# untitled.net
KiCad netlist of a schematic drawn in EAGLE
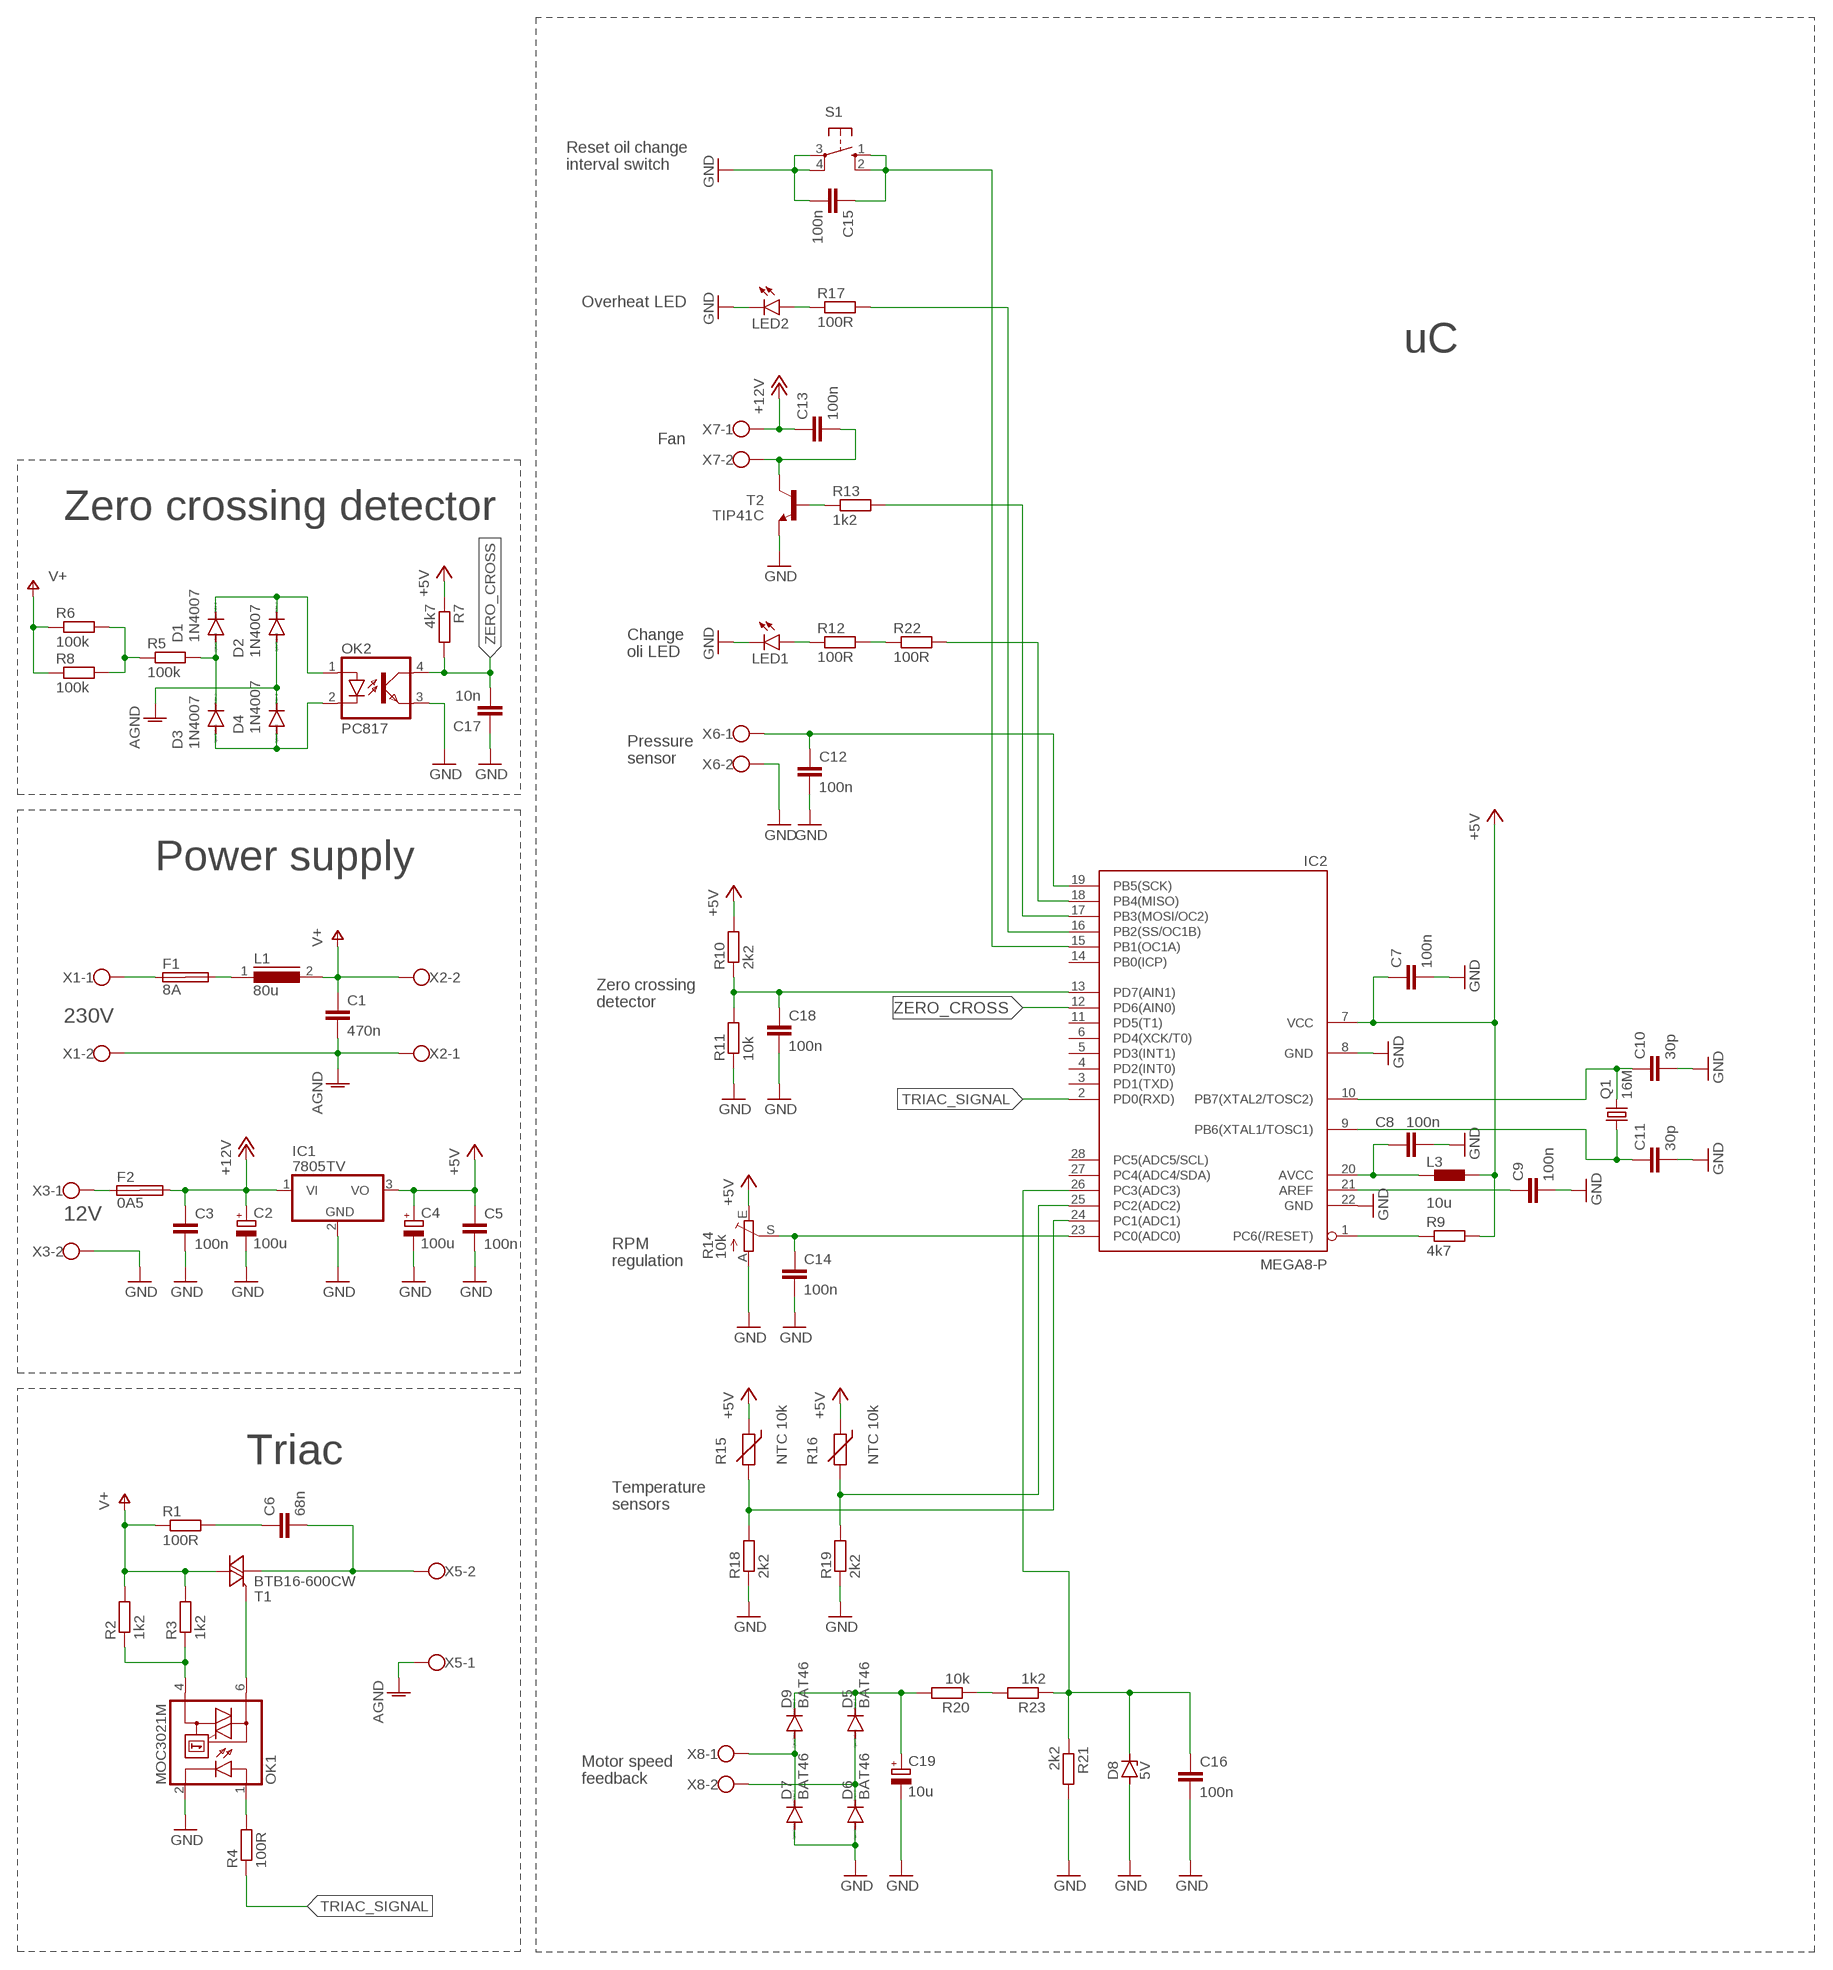
[diagram p0: schematic, sheet 1]

(export (version "E")
  (design (tool "Eeschema 10.0.6"))
  (components
    (comp (ref "C1")
      (value "470n")
      (footprint "eagle-import:C22.5B7")
      (libsource (lib "eagle-import") (part "C22/7"))
    )
    (comp (ref "C2")
      (value "100u")
      (footprint "eagle-import:E3,5-8")
      (libsource (lib "eagle-import") (part "CPOL-EUE3.5-8"))
    )
    (comp (ref "C3")
      (value "100n")
      (footprint "eagle-import:C5B3")
      (libsource (lib "eagle-import") (part "C5/3"))
    )
    (comp (ref "C4")
      (value "100u")
      (footprint "eagle-import:E3,5-8")
      (libsource (lib "eagle-import") (part "CPOL-EUE3.5-8"))
    )
    (comp (ref "C5")
      (value "100n")
      (footprint "eagle-import:C5B3")
      (libsource (lib "eagle-import") (part "C5/3"))
    )
    (comp (ref "C6")
      (value "68n")
      (footprint "eagle-import:C150-084X183")
      (libsource (lib "eagle-import") (part "C-EU150-084X183"))
    )
    (comp (ref "C7")
      (value "100n")
      (footprint "eagle-import:C5B3")
      (libsource (lib "eagle-import") (part "C5/3"))
    )
    (comp (ref "C8")
      (value "100n")
      (footprint "eagle-import:C5B3")
      (libsource (lib "eagle-import") (part "C5/3"))
    )
    (comp (ref "C9")
      (value "100n")
      (footprint "eagle-import:C5B3")
      (libsource (lib "eagle-import") (part "C5/3"))
    )
    (comp (ref "C10")
      (value "30p")
      (footprint "eagle-import:C5B3")
      (libsource (lib "eagle-import") (part "C5/3"))
    )
    (comp (ref "C11")
      (value "30p")
      (footprint "eagle-import:C5B3")
      (libsource (lib "eagle-import") (part "C5/3"))
    )
    (comp (ref "C12")
      (value "100n")
      (footprint "eagle-import:C5B3")
      (libsource (lib "eagle-import") (part "C5/3"))
    )
    (comp (ref "C13")
      (value "100n")
      (footprint "eagle-import:C5B3")
      (libsource (lib "eagle-import") (part "C5/3"))
    )
    (comp (ref "C14")
      (value "100n")
      (footprint "eagle-import:C5B3")
      (libsource (lib "eagle-import") (part "C5/3"))
    )
    (comp (ref "C15")
      (value "100n")
      (footprint "eagle-import:C5B3")
      (libsource (lib "eagle-import") (part "C5/3"))
    )
    (comp (ref "C16")
      (value "100n")
      (footprint "eagle-import:C5B3")
      (libsource (lib "eagle-import") (part "C5/3"))
    )
    (comp (ref "C17")
      (value "10n")
      (footprint "eagle-import:C5B3")
      (libsource (lib "eagle-import") (part "C5/3"))
    )
    (comp (ref "C18")
      (value "100n")
      (footprint "eagle-import:C5B3")
      (libsource (lib "eagle-import") (part "C5/3"))
    )
    (comp (ref "C19")
      (value "10u")
      (footprint "eagle-import:E2,5-6")
      (libsource (lib "eagle-import") (part "CPOL-EUE2.5-6"))
    )
    (comp (ref "D1")
      (value "1N4007")
      (footprint "eagle-import:DO41-10")
      (libsource (lib "eagle-import") (part "1N4933"))
    )
    (comp (ref "D2")
      (value "1N4007")
      (footprint "eagle-import:DO41-10")
      (libsource (lib "eagle-import") (part "1N4933"))
    )
    (comp (ref "D3")
      (value "1N4007")
      (footprint "eagle-import:DO41-10")
      (libsource (lib "eagle-import") (part "1N4933"))
    )
    (comp (ref "D4")
      (value "1N4007")
      (footprint "eagle-import:DO41-10")
      (libsource (lib "eagle-import") (part "1N4933"))
    )
    (comp (ref "D5")
      (value "BAT46")
      (footprint "eagle-import:DO34-7")
      (libsource (lib "eagle-import") (part "BAS15"))
    )
    (comp (ref "D6")
      (value "BAT46")
      (footprint "eagle-import:DO34-7")
      (libsource (lib "eagle-import") (part "BAS15"))
    )
    (comp (ref "D7")
      (value "BAT46")
      (footprint "eagle-import:DO34-7")
      (libsource (lib "eagle-import") (part "BAS15"))
    )
    (comp (ref "D8")
      (value "5V")
      (footprint "eagle-import:DO34Z7")
      (libsource (lib "eagle-import") (part "ZENER-DIODEDO34-7"))
    )
    (comp (ref "D9")
      (value "BAT46")
      (footprint "eagle-import:DO34-7")
      (libsource (lib "eagle-import") (part "BAS15"))
    )
    (comp (ref "F1")
      (value "8A")
      (footprint "eagle-import:SHK20L")
      (libsource (lib "eagle-import") (part "SHK20L"))
    )
    (comp (ref "F2")
      (value "0A5")
      (footprint "eagle-import:SHK20L")
      (libsource (lib "eagle-import") (part "SHK20L"))
    )
    (comp (ref "IC1")
      (value "7805TV")
      (footprint "eagle-import:TO220V")
      (libsource (lib "eagle-import") (part "78TV05"))
    )
    (comp (ref "IC2")
      (value "MEGA8-P")
      (footprint "eagle-import:DIL28-3")
      (libsource (lib "eagle-import") (part "MEGA8-P"))
    )
    (comp (ref "L1")
      (value "80u")
      (footprint "eagle-import:SFT1030")
      (libsource (lib "eagle-import") (part "SFT1030"))
    )
    (comp (ref "L3")
      (value "10u")
      (footprint "eagle-import:BL01RN1A")
      (libsource (lib "eagle-import") (part "BL01RN1A"))
    )
    (comp (ref "LED1")
      (value "LED5MM")
      (footprint "eagle-import:LED5MM")
      (libsource (lib "eagle-import") (part "LED5MM"))
    )
    (comp (ref "LED2")
      (value "LED5MM")
      (footprint "eagle-import:LED5MM")
      (libsource (lib "eagle-import") (part "LED5MM"))
    )
    (comp (ref "OK1")
      (value "MOC3021M")
      (footprint "eagle-import:DIL06")
      (fields (field (name "MF") "FAIRCHILD SEMICONDUCTOR") (field (name "MPN") "MOC3021-M"))
      (libsource (lib "eagle-import") (part "MOC30M21"))
    )
    (comp (ref "OK2")
      (value "PC817")
      (footprint "eagle-import:DIL04")
      (fields (field (name "MPN") "PC817X4J000F"))
      (libsource (lib "eagle-import") (part "PC817"))
    )
    (comp (ref "Q1")
      (value "16M")
      (footprint "eagle-import:HC49_S")
      (libsource (lib "eagle-import") (part "CRYSTALHC49S"))
    )
    (comp (ref "R1")
      (value "100R")
      (footprint "eagle-import:0204_7")
      (libsource (lib "eagle-import") (part "R-EU_0204/7"))
    )
    (comp (ref "R2")
      (value "1k2")
      (footprint "eagle-import:0204_7")
      (libsource (lib "eagle-import") (part "R-EU_0204/7"))
    )
    (comp (ref "R3")
      (value "1k2")
      (footprint "eagle-import:0204_7")
      (libsource (lib "eagle-import") (part "R-EU_0204/7"))
    )
    (comp (ref "R4")
      (value "100R")
      (footprint "eagle-import:0204_7")
      (libsource (lib "eagle-import") (part "R-EU_0204/7"))
    )
    (comp (ref "R5")
      (value "100k")
      (footprint "eagle-import:0204_7")
      (libsource (lib "eagle-import") (part "R-EU_0204/7"))
    )
    (comp (ref "R6")
      (value "100k")
      (footprint "eagle-import:0204_7")
      (libsource (lib "eagle-import") (part "R-EU_0204/7"))
    )
    (comp (ref "R7")
      (value "4k7")
      (footprint "eagle-import:0204_7")
      (libsource (lib "eagle-import") (part "R-EU_0204/7"))
    )
    (comp (ref "R8")
      (value "100k")
      (footprint "eagle-import:0204_7")
      (libsource (lib "eagle-import") (part "R-EU_0204/7"))
    )
    (comp (ref "R9")
      (value "4k7")
      (footprint "eagle-import:0204_7")
      (libsource (lib "eagle-import") (part "R-EU_0204/7"))
    )
    (comp (ref "R10")
      (value "2k2")
      (footprint "eagle-import:0204_7")
      (libsource (lib "eagle-import") (part "R-EU_0204/7"))
    )
    (comp (ref "R11")
      (value "10k")
      (footprint "eagle-import:0204_7")
      (libsource (lib "eagle-import") (part "R-EU_0204/7"))
    )
    (comp (ref "R12")
      (value "100R")
      (footprint "eagle-import:0204_7")
      (libsource (lib "eagle-import") (part "R-EU_0204/7"))
    )
    (comp (ref "R13")
      (value "1k2")
      (footprint "eagle-import:0204_7")
      (libsource (lib "eagle-import") (part "R-EU_0204/7"))
    )
    (comp (ref "R14")
      (value "10k")
      (footprint "eagle-import:RJ9W")
      (libsource (lib "eagle-import") (part "TRIM_EU-RJ9W"))
    )
    (comp (ref "R15")
      (value "NTC 10k")
      (footprint "eagle-import:R-7,5")
      (libsource (lib "eagle-import") (part "THERMISTOR-7,5"))
    )
    (comp (ref "R16")
      (value "NTC 10k")
      (footprint "eagle-import:R-7,5")
      (libsource (lib "eagle-import") (part "THERMISTOR-7,5"))
    )
    (comp (ref "R17")
      (value "100R")
      (footprint "eagle-import:0204_7")
      (libsource (lib "eagle-import") (part "R-EU_0204/7"))
    )
    (comp (ref "R18")
      (value "2k2")
      (footprint "eagle-import:0204_7")
      (libsource (lib "eagle-import") (part "R-EU_0204/7"))
    )
    (comp (ref "R19")
      (value "2k2")
      (footprint "eagle-import:0204_7")
      (libsource (lib "eagle-import") (part "R-EU_0204/7"))
    )
    (comp (ref "R20")
      (value "10k")
      (footprint "eagle-import:0204_7")
      (libsource (lib "eagle-import") (part "R-EU_0204/7"))
    )
    (comp (ref "R21")
      (value "2k2")
      (footprint "eagle-import:0204_7")
      (libsource (lib "eagle-import") (part "R-EU_0204/7"))
    )
    (comp (ref "R22")
      (value "100R")
      (footprint "eagle-import:0204_7")
      (libsource (lib "eagle-import") (part "R-EU_0204/7"))
    )
    (comp (ref "R23")
      (value "1k2")
      (footprint "eagle-import:0204_7")
      (libsource (lib "eagle-import") (part "R-EU_0204/7"))
    )
    (comp (ref "S1")
      (value "10-XX")
      (footprint "eagle-import:B3F-10XX")
      (fields (field (name "MPN") "B3F-1000"))
      (libsource (lib "eagle-import") (part "10-XX"))
    )
    (comp (ref "T1")
      (value "BTB16-600CW")
      (footprint "eagle-import:TO220BV")
      (libsource (lib "eagle-import") (part "BT138-V"))
    )
    (comp (ref "T2")
      (value "TIP41C")
      (footprint "eagle-import:TO220V")
      (libsource (lib "eagle-import") (part "-NPN-TO220V"))
    )
    (comp (ref "X1")
      (value "W237-102")
      (footprint "eagle-import:W237-102")
      (fields (field (name "MPN") "237-102"))
      (libsource (lib "eagle-import") (part "W237-102"))
    )
    (comp (ref "X2")
      (value "W237-102")
      (footprint "eagle-import:W237-102")
      (fields (field (name "MPN") "237-102"))
      (libsource (lib "eagle-import") (part "W237-102"))
    )
    (comp (ref "X3")
      (value "W237-102")
      (footprint "eagle-import:W237-102")
      (fields (field (name "MPN") "237-102"))
      (libsource (lib "eagle-import") (part "W237-102"))
    )
    (comp (ref "X5")
      (value "W237-102")
      (footprint "eagle-import:W237-102")
      (fields (field (name "MPN") "237-102"))
      (libsource (lib "eagle-import") (part "W237-102"))
    )
    (comp (ref "X6")
      (value "W237-102")
      (footprint "eagle-import:W237-102")
      (fields (field (name "MPN") "237-102"))
      (libsource (lib "eagle-import") (part "W237-102"))
    )
    (comp (ref "X7")
      (value "W237-102")
      (footprint "eagle-import:W237-102")
      (fields (field (name "MPN") "237-102"))
      (libsource (lib "eagle-import") (part "W237-102"))
    )
    (comp (ref "X8")
      (value "W237-102")
      (footprint "eagle-import:W237-102")
      (fields (field (name "MPN") "237-102"))
      (libsource (lib "eagle-import") (part "W237-102"))
    )
  )
  (nets
    (net (code "1") (name "+5V") (class "Default")
      (node (ref "C4") (pin "+") (pinfunction "+_+") (pintype "passive"))
      (node (ref "C5") (pin "1") (pinfunction "1_1") (pintype "passive"))
      (node (ref "C7") (pin "1") (pinfunction "1_1") (pintype "passive"))
      (node (ref "IC1") (pin "3") (pinfunction "VO_3") (pintype "passive"))
      (node (ref "IC2") (pin "7") (pinfunction "VCC_7") (pintype "power_in"))
      (node (ref "L3") (pin "2") (pinfunction "2_2") (pintype "passive"))
      (node (ref "R10") (pin "2") (pinfunction "2_2") (pintype "passive"))
      (node (ref "R14") (pin "E") (pinfunction "E_E") (pintype "passive"))
      (node (ref "R15") (pin "1") (pinfunction "1_1") (pintype "passive"))
      (node (ref "R16") (pin "1") (pinfunction "1_1") (pintype "passive"))
      (node (ref "R7") (pin "1") (pinfunction "1_1") (pintype "passive"))
      (node (ref "R9") (pin "2") (pinfunction "2_2") (pintype "passive"))
    )
    (net (code "2") (name "+12V") (class "Default")
      (node (ref "C13") (pin "1") (pinfunction "1_1") (pintype "passive"))
      (node (ref "C2") (pin "+") (pinfunction "+_+") (pintype "passive"))
      (node (ref "C3") (pin "1") (pinfunction "1_1") (pintype "passive"))
      (node (ref "F2") (pin "2A") (pinfunction "2A_2A") (pintype "passive"))
      (node (ref "IC1") (pin "1") (pinfunction "VI_1") (pintype "input"))
      (node (ref "X7") (pin "1") (pinfunction "KL_1") (pintype "passive"))
    )
    (net (code "3") (name "AGND") (class "Default")
      (node (ref "C1") (pin "2") (pinfunction "2_2") (pintype "passive"))
      (node (ref "D2") (pin "A") (pinfunction "A_A") (pintype "passive"))
      (node (ref "D4") (pin "C") (pinfunction "C_C") (pintype "passive"))
      (node (ref "X1") (pin "2") (pinfunction "KL_2") (pintype "passive"))
      (node (ref "X2") (pin "1") (pinfunction "KL_1") (pintype "passive"))
      (node (ref "X5") (pin "1") (pinfunction "KL_1") (pintype "passive"))
    )
    (net (code "4") (name "GND") (class "Default")
      (node (ref "C10") (pin "2") (pinfunction "2_2") (pintype "passive"))
      (node (ref "C11") (pin "2") (pinfunction "2_2") (pintype "passive"))
      (node (ref "C12") (pin "2") (pinfunction "2_2") (pintype "passive"))
      (node (ref "C14") (pin "2") (pinfunction "2_2") (pintype "passive"))
      (node (ref "C15") (pin "2") (pinfunction "2_2") (pintype "passive"))
      (node (ref "C16") (pin "2") (pinfunction "2_2") (pintype "passive"))
      (node (ref "C17") (pin "1") (pinfunction "1_1") (pintype "passive"))
      (node (ref "C18") (pin "2") (pinfunction "2_2") (pintype "passive"))
      (node (ref "C19") (pin "-") (pinfunction "-_-") (pintype "passive"))
      (node (ref "C2") (pin "-") (pinfunction "-_-") (pintype "passive"))
      (node (ref "C3") (pin "2") (pinfunction "2_2") (pintype "passive"))
      (node (ref "C4") (pin "-") (pinfunction "-_-") (pintype "passive"))
      (node (ref "C5") (pin "2") (pinfunction "2_2") (pintype "passive"))
      (node (ref "C7") (pin "2") (pinfunction "2_2") (pintype "passive"))
      (node (ref "C8") (pin "2") (pinfunction "2_2") (pintype "passive"))
      (node (ref "C9") (pin "2") (pinfunction "2_2") (pintype "passive"))
      (node (ref "D6") (pin "A") (pinfunction "A_A") (pintype "passive"))
      (node (ref "D7") (pin "A") (pinfunction "A_A") (pintype "passive"))
      (node (ref "D8") (pin "A") (pinfunction "A_A") (pintype "passive"))
      (node (ref "IC1") (pin "2") (pinfunction "GND_2") (pintype "passive"))
      (node (ref "IC2") (pin "22") (pinfunction "GND_22") (pintype "power_in"))
      (node (ref "IC2") (pin "8") (pinfunction "GND_8") (pintype "power_in"))
      (node (ref "LED1") (pin "K") (pinfunction "C_K") (pintype "passive"))
      (node (ref "LED2") (pin "K") (pinfunction "C_K") (pintype "passive"))
      (node (ref "OK1") (pin "2") (pinfunction "C_2") (pintype "passive"))
      (node (ref "OK2") (pin "3") (pinfunction "EMIT_3") (pintype "passive"))
      (node (ref "R11") (pin "1") (pinfunction "1_1") (pintype "passive"))
      (node (ref "R14") (pin "A") (pinfunction "A_A") (pintype "passive"))
      (node (ref "R18") (pin "1") (pinfunction "1_1") (pintype "passive"))
      (node (ref "R19") (pin "1") (pinfunction "1_1") (pintype "passive"))
      (node (ref "R21") (pin "2") (pinfunction "2_2") (pintype "passive"))
      (node (ref "S1") (pin "3") (pinfunction "P_3") (pintype "passive"))
      (node (ref "S1") (pin "4") (pinfunction "P1_4") (pintype "passive"))
      (node (ref "T2") (pin "3") (pinfunction "E_3") (pintype "passive"))
      (node (ref "X3") (pin "2") (pinfunction "KL_2") (pintype "passive"))
      (node (ref "X6") (pin "2") (pinfunction "KL_2") (pintype "passive"))
    )
    (net (code "5") (name "Net-(C6-Pad1)") (class "Default")
      (node (ref "C6") (pin "1") (pinfunction "1_1") (pintype "passive"))
      (node (ref "R1") (pin "2") (pinfunction "2_2") (pintype "passive"))
    )
    (net (code "6") (name "Net-(C19-Pad+)") (class "Default")
      (node (ref "C19") (pin "+") (pinfunction "+_+") (pintype "passive"))
      (node (ref "D5") (pin "C") (pinfunction "C_C") (pintype "passive"))
      (node (ref "D9") (pin "C") (pinfunction "C_C") (pintype "passive"))
      (node (ref "R20") (pin "2") (pinfunction "2_2") (pintype "passive"))
    )
    (net (code "7") (name "Net-(D1-PadA)") (class "Default")
      (node (ref "D1") (pin "A") (pinfunction "A_A") (pintype "passive"))
      (node (ref "D3") (pin "C") (pinfunction "C_C") (pintype "passive"))
      (node (ref "R5") (pin "2") (pinfunction "2_2") (pintype "passive"))
    )
    (net (code "8") (name "Net-(F1-Pad2A)") (class "Default")
      (node (ref "F1") (pin "2A") (pinfunction "2A_2A") (pintype "passive"))
      (node (ref "L1") (pin "1") (pinfunction "1_1") (pintype "passive"))
    )
    (net (code "9") (name "Net-(IC2-AREF)") (class "Default")
      (node (ref "C9") (pin "1") (pinfunction "1_1") (pintype "passive"))
      (node (ref "IC2") (pin "21") (pinfunction "AREF_21") (pintype "passive"))
    )
    (net (code "10") (name "Net-(IC2-AVCC)") (class "Default")
      (node (ref "C8") (pin "1") (pinfunction "1_1") (pintype "passive"))
      (node (ref "IC2") (pin "20") (pinfunction "AVCC_20") (pintype "power_in"))
      (node (ref "L3") (pin "1") (pinfunction "1_1") (pintype "passive"))
    )
    (net (code "11") (name "Net-(IC2-PB1(OC1A))") (class "Default")
      (node (ref "C15") (pin "1") (pinfunction "1_1") (pintype "passive"))
      (node (ref "IC2") (pin "15") (pinfunction "PB1(OC1A)_15") (pintype "bidirectional"))
      (node (ref "S1") (pin "1") (pinfunction "S_1") (pintype "passive"))
      (node (ref "S1") (pin "2") (pinfunction "S1_2") (pintype "passive"))
    )
    (net (code "12") (name "Net-(IC2-PB2(SS{slash}OC1B))") (class "Default")
      (node (ref "IC2") (pin "16") (pinfunction "PB2(SS/OC1B)_16") (pintype "bidirectional"))
      (node (ref "R17") (pin "2") (pinfunction "2_2") (pintype "passive"))
    )
    (net (code "13") (name "Net-(IC2-PB3(MOSI{slash}OC2))") (class "Default")
      (node (ref "IC2") (pin "17") (pinfunction "PB3(MOSI/OC2)_17") (pintype "bidirectional"))
      (node (ref "R13") (pin "2") (pinfunction "2_2") (pintype "passive"))
    )
    (net (code "14") (name "Net-(IC2-PB4(MISO))") (class "Default")
      (node (ref "IC2") (pin "18") (pinfunction "PB4(MISO)_18") (pintype "bidirectional"))
      (node (ref "R22") (pin "2") (pinfunction "2_2") (pintype "passive"))
    )
    (net (code "15") (name "Net-(IC2-PB5(SCK))") (class "Default")
      (node (ref "C12") (pin "1") (pinfunction "1_1") (pintype "passive"))
      (node (ref "IC2") (pin "19") (pinfunction "PB5(SCK)_19") (pintype "bidirectional"))
      (node (ref "X6") (pin "1") (pinfunction "KL_1") (pintype "passive"))
    )
    (net (code "16") (name "Net-(IC2-PB6(XTAL1{slash}TOSC1))") (class "Default")
      (node (ref "C11") (pin "1") (pinfunction "1_1") (pintype "passive"))
      (node (ref "IC2") (pin "9") (pinfunction "PB6(XTAL1/TOSC1)_9") (pintype "bidirectional"))
      (node (ref "Q1") (pin "1") (pinfunction "1_1") (pintype "passive"))
    )
    (net (code "17") (name "Net-(IC2-PB7(XTAL2{slash}TOSC2))") (class "Default")
      (node (ref "C10") (pin "1") (pinfunction "1_1") (pintype "passive"))
      (node (ref "IC2") (pin "10") (pinfunction "PB7(XTAL2/TOSC2)_10") (pintype "bidirectional"))
      (node (ref "Q1") (pin "2") (pinfunction "2_2") (pintype "passive"))
    )
    (net (code "18") (name "Net-(IC2-PC0(ADC0))") (class "Default")
      (node (ref "C14") (pin "1") (pinfunction "1_1") (pintype "passive"))
      (node (ref "IC2") (pin "23") (pinfunction "PC0(ADC0)_23") (pintype "bidirectional"))
      (node (ref "R14") (pin "S") (pinfunction "S_S") (pintype "passive"))
    )
    (net (code "19") (name "Net-(IC2-PC1(ADC1))") (class "Default")
      (node (ref "IC2") (pin "24") (pinfunction "PC1(ADC1)_24") (pintype "bidirectional"))
      (node (ref "R15") (pin "2") (pinfunction "2_2") (pintype "passive"))
      (node (ref "R18") (pin "2") (pinfunction "2_2") (pintype "passive"))
    )
    (net (code "20") (name "Net-(IC2-PC2(ADC2))") (class "Default")
      (node (ref "IC2") (pin "25") (pinfunction "PC2(ADC2)_25") (pintype "bidirectional"))
      (node (ref "R16") (pin "2") (pinfunction "2_2") (pintype "passive"))
      (node (ref "R19") (pin "2") (pinfunction "2_2") (pintype "passive"))
    )
    (net (code "21") (name "Net-(IC2-PC3(ADC3))") (class "Default")
      (node (ref "C16") (pin "1") (pinfunction "1_1") (pintype "passive"))
      (node (ref "D8") (pin "C") (pinfunction "C_C") (pintype "passive"))
      (node (ref "IC2") (pin "26") (pinfunction "PC3(ADC3)_26") (pintype "bidirectional"))
      (node (ref "R21") (pin "1") (pinfunction "1_1") (pintype "passive"))
      (node (ref "R23") (pin "1") (pinfunction "1_1") (pintype "passive"))
    )
    (net (code "22") (name "Net-(IC2-PC6({slash}RESET))") (class "Default")
      (node (ref "IC2") (pin "1") (pinfunction "PC6(/RESET)_1") (pintype "bidirectional"))
      (node (ref "R9") (pin "1") (pinfunction "1_1") (pintype "passive"))
    )
    (net (code "23") (name "Net-(IC2-PD7(AIN1))") (class "Default")
      (node (ref "C18") (pin "1") (pinfunction "1_1") (pintype "passive"))
      (node (ref "IC2") (pin "13") (pinfunction "PD7(AIN1)_13") (pintype "bidirectional"))
      (node (ref "R10") (pin "1") (pinfunction "1_1") (pintype "passive"))
      (node (ref "R11") (pin "2") (pinfunction "2_2") (pintype "passive"))
    )
    (net (code "24") (name "Net-(LED1-PadA)") (class "Default")
      (node (ref "LED1") (pin "A") (pinfunction "A_A") (pintype "passive"))
      (node (ref "R12") (pin "1") (pinfunction "1_1") (pintype "passive"))
    )
    (net (code "25") (name "Net-(LED2-PadA)") (class "Default")
      (node (ref "LED2") (pin "A") (pinfunction "A_A") (pintype "passive"))
      (node (ref "R17") (pin "1") (pinfunction "1_1") (pintype "passive"))
    )
    (net (code "26") (name "Net-(OK1-A)") (class "Default")
      (node (ref "OK1") (pin "1") (pinfunction "A_1") (pintype "passive"))
      (node (ref "R4") (pin "2") (pinfunction "2_2") (pintype "passive"))
    )
    (net (code "27") (name "Net-(OK1-A1)") (class "Default")
      (node (ref "OK1") (pin "4") (pinfunction "A1_4") (pintype "passive"))
      (node (ref "R2") (pin "1") (pinfunction "1_1") (pintype "passive"))
      (node (ref "R3") (pin "1") (pinfunction "1_1") (pintype "passive"))
    )
    (net (code "28") (name "Net-(OK1-A2)") (class "Default")
      (node (ref "OK1") (pin "6") (pinfunction "A2_6") (pintype "passive"))
      (node (ref "T1") (pin "G") (pinfunction "G_G") (pintype "passive"))
    )
    (net (code "29") (name "Net-(OK2-A)") (class "Default")
      (node (ref "D1") (pin "C") (pinfunction "C_C") (pintype "passive"))
      (node (ref "D2") (pin "C") (pinfunction "C_C") (pintype "passive"))
      (node (ref "OK2") (pin "1") (pinfunction "A_1") (pintype "passive"))
    )
    (net (code "30") (name "Net-(OK2-C)") (class "Default")
      (node (ref "D3") (pin "A") (pinfunction "A_A") (pintype "passive"))
      (node (ref "D4") (pin "A") (pinfunction "A_A") (pintype "passive"))
      (node (ref "OK2") (pin "2") (pinfunction "C_2") (pintype "passive"))
    )
    (net (code "31") (name "Net-(R5-Pad1)") (class "Default")
      (node (ref "R5") (pin "1") (pinfunction "1_1") (pintype "passive"))
      (node (ref "R6") (pin "2") (pinfunction "2_2") (pintype "passive"))
      (node (ref "R8") (pin "2") (pinfunction "2_2") (pintype "passive"))
    )
    (net (code "32") (name "Net-(R12-Pad2)") (class "Default")
      (node (ref "R12") (pin "2") (pinfunction "2_2") (pintype "passive"))
      (node (ref "R22") (pin "1") (pinfunction "1_1") (pintype "passive"))
    )
    (net (code "33") (name "Net-(R20-Pad1)") (class "Default")
      (node (ref "R20") (pin "1") (pinfunction "1_1") (pintype "passive"))
      (node (ref "R23") (pin "2") (pinfunction "2_2") (pintype "passive"))
    )
    (net (code "34") (name "Net-(T1-A1)") (class "Default")
      (node (ref "C6") (pin "2") (pinfunction "2_2") (pintype "passive"))
      (node (ref "T1") (pin "T1") (pinfunction "A1_T1") (pintype "passive"))
      (node (ref "X5") (pin "2") (pinfunction "KL_2") (pintype "passive"))
    )
    (net (code "35") (name "Net-(T2-B)") (class "Default")
      (node (ref "R13") (pin "1") (pinfunction "1_1") (pintype "passive"))
      (node (ref "T2") (pin "1") (pinfunction "B_1") (pintype "passive"))
    )
    (net (code "36") (name "Net-(T2-C)") (class "Default")
      (node (ref "C13") (pin "2") (pinfunction "2_2") (pintype "passive"))
      (node (ref "T2") (pin "2") (pinfunction "C_2") (pintype "passive"))
      (node (ref "X7") (pin "2") (pinfunction "KL_2") (pintype "passive"))
    )
    (net (code "37") (name "Net-(X1A-KL)") (class "Default")
      (node (ref "F1") (pin "1A") (pinfunction "1A_1A") (pintype "passive"))
      (node (ref "X1") (pin "1") (pinfunction "KL_1") (pintype "passive"))
    )
    (net (code "38") (name "Net-(X3A-KL)") (class "Default")
      (node (ref "F2") (pin "1A") (pinfunction "1A_1A") (pintype "passive"))
      (node (ref "X3") (pin "1") (pinfunction "KL_1") (pintype "passive"))
    )
    (net (code "39") (name "Net-(X8A-KL)") (class "Default")
      (node (ref "D7") (pin "C") (pinfunction "C_C") (pintype "passive"))
      (node (ref "D9") (pin "A") (pinfunction "A_A") (pintype "passive"))
      (node (ref "X8") (pin "1") (pinfunction "KL_1") (pintype "passive"))
    )
    (net (code "40") (name "Net-(X8B-KL)") (class "Default")
      (node (ref "D5") (pin "A") (pinfunction "A_A") (pintype "passive"))
      (node (ref "D6") (pin "C") (pinfunction "C_C") (pintype "passive"))
      (node (ref "X8") (pin "2") (pinfunction "KL_2") (pintype "passive"))
    )
    (net (code "41") (name "TRIAC_SIGNAL") (class "Default")
      (node (ref "IC2") (pin "2") (pinfunction "PD0(RXD)_2") (pintype "bidirectional"))
      (node (ref "R4") (pin "1") (pinfunction "1_1") (pintype "passive"))
    )
    (net (code "42") (name "V+") (class "Default")
      (node (ref "C1") (pin "1") (pinfunction "1_1") (pintype "passive"))
      (node (ref "L1") (pin "2") (pinfunction "2_2") (pintype "passive"))
      (node (ref "R1") (pin "1") (pinfunction "1_1") (pintype "passive"))
      (node (ref "R2") (pin "2") (pinfunction "2_2") (pintype "passive"))
      (node (ref "R3") (pin "2") (pinfunction "2_2") (pintype "passive"))
      (node (ref "R6") (pin "1") (pinfunction "1_1") (pintype "passive"))
      (node (ref "R8") (pin "1") (pinfunction "1_1") (pintype "passive"))
      (node (ref "T1") (pin "T2") (pinfunction "A2_T2") (pintype "passive"))
      (node (ref "X2") (pin "2") (pinfunction "KL_2") (pintype "passive"))
    )
    (net (code "43") (name "ZERO_CROSS") (class "Default")
      (node (ref "C17") (pin "2") (pinfunction "2_2") (pintype "passive"))
      (node (ref "IC2") (pin "12") (pinfunction "PD6(AIN0)_12") (pintype "bidirectional"))
      (node (ref "OK2") (pin "4") (pinfunction "COL_4") (pintype "passive"))
      (node (ref "R7") (pin "2") (pinfunction "2_2") (pintype "passive"))
    )
    (net (code "44") (name "unconnected-(F1-Pad1B)") (class "Default")
      (node (ref "F1") (pin "1B") (pinfunction "1B_1B") (pintype "passive"))
    )
    (net (code "45") (name "unconnected-(F1-Pad2B)") (class "Default")
      (node (ref "F1") (pin "2B") (pinfunction "2B_2B") (pintype "passive"))
    )
    (net (code "46") (name "unconnected-(F2-Pad1B)") (class "Default")
      (node (ref "F2") (pin "1B") (pinfunction "1B_1B") (pintype "passive"))
    )
    (net (code "47") (name "unconnected-(F2-Pad2B)") (class "Default")
      (node (ref "F2") (pin "2B") (pinfunction "2B_2B") (pintype "passive"))
    )
    (net (code "48") (name "unconnected-(IC2-PB0(ICP)-Pad14)") (class "Default")
      (node (ref "IC2") (pin "14") (pinfunction "PB0(ICP)_14") (pintype "bidirectional"))
    )
    (net (code "49") (name "unconnected-(IC2-PC4(ADC4{slash}SDA)-Pad27)") (class "Default")
      (node (ref "IC2") (pin "27") (pinfunction "PC4(ADC4/SDA)_27") (pintype "bidirectional"))
    )
    (net (code "50") (name "unconnected-(IC2-PC5(ADC5{slash}SCL)-Pad28)") (class "Default")
      (node (ref "IC2") (pin "28") (pinfunction "PC5(ADC5/SCL)_28") (pintype "bidirectional"))
    )
    (net (code "51") (name "unconnected-(IC2-PD1(TXD)-Pad3)") (class "Default")
      (node (ref "IC2") (pin "3") (pinfunction "PD1(TXD)_3") (pintype "bidirectional"))
    )
    (net (code "52") (name "unconnected-(IC2-PD2(INT0)-Pad4)") (class "Default")
      (node (ref "IC2") (pin "4") (pinfunction "PD2(INT0)_4") (pintype "bidirectional"))
    )
    (net (code "53") (name "unconnected-(IC2-PD3(INT1)-Pad5)") (class "Default")
      (node (ref "IC2") (pin "5") (pinfunction "PD3(INT1)_5") (pintype "bidirectional"))
    )
    (net (code "54") (name "unconnected-(IC2-PD4(XCK{slash}T0)-Pad6)") (class "Default")
      (node (ref "IC2") (pin "6") (pinfunction "PD4(XCK/T0)_6") (pintype "bidirectional"))
    )
    (net (code "55") (name "unconnected-(IC2-PD5(T1)-Pad11)") (class "Default")
      (node (ref "IC2") (pin "11") (pinfunction "PD5(T1)_11") (pintype "bidirectional"))
    )
  )
)
